# Main_BoardV4.net
KiCad netlist of a schematic drawn in EAGLE
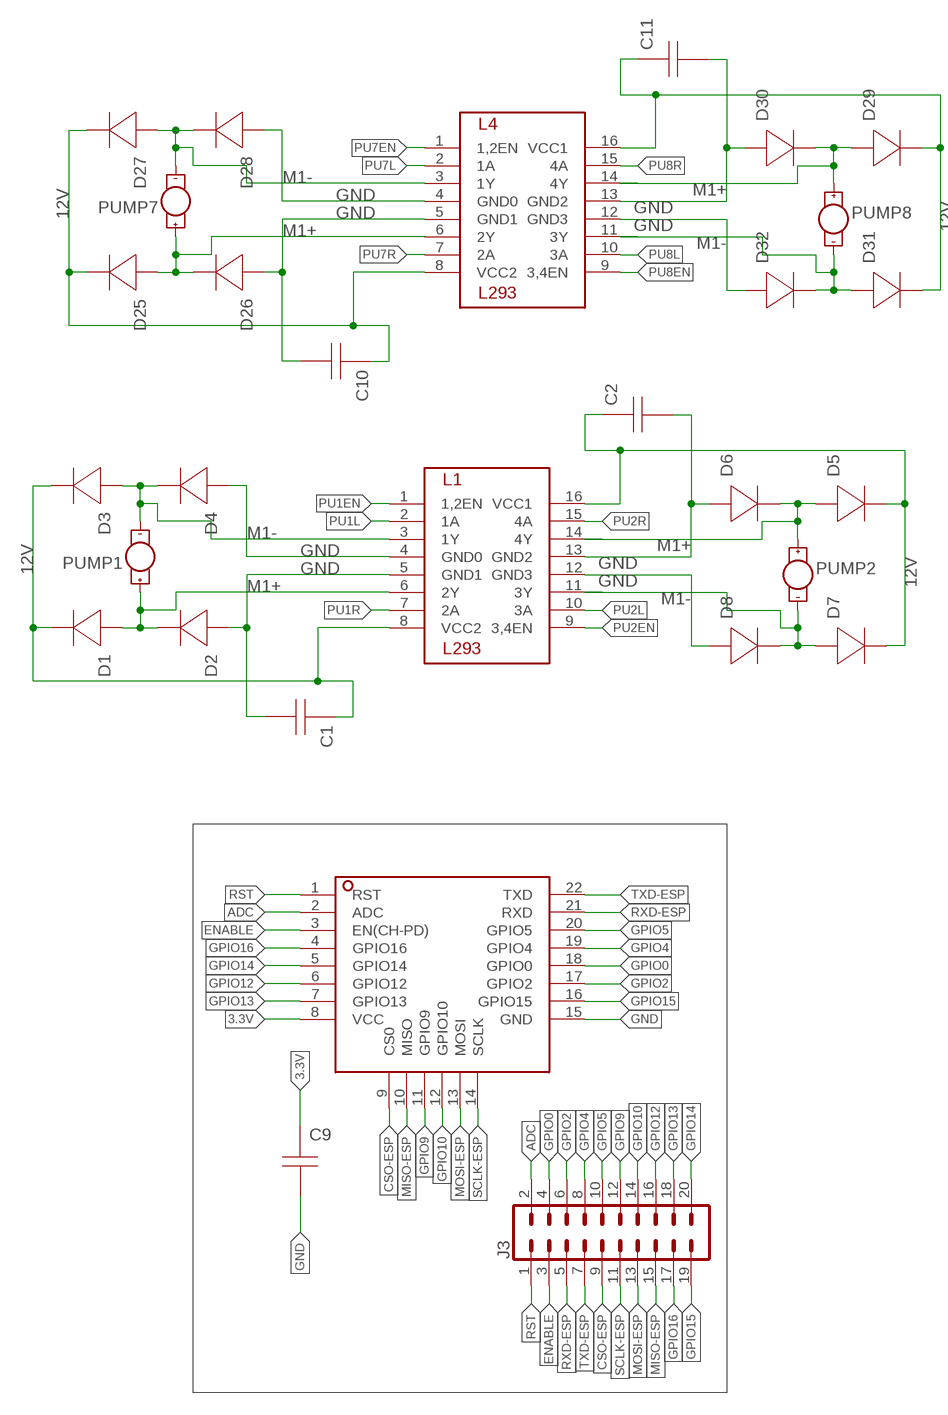
[diagram p0: schematic, sheet 1, part 1 of 2]
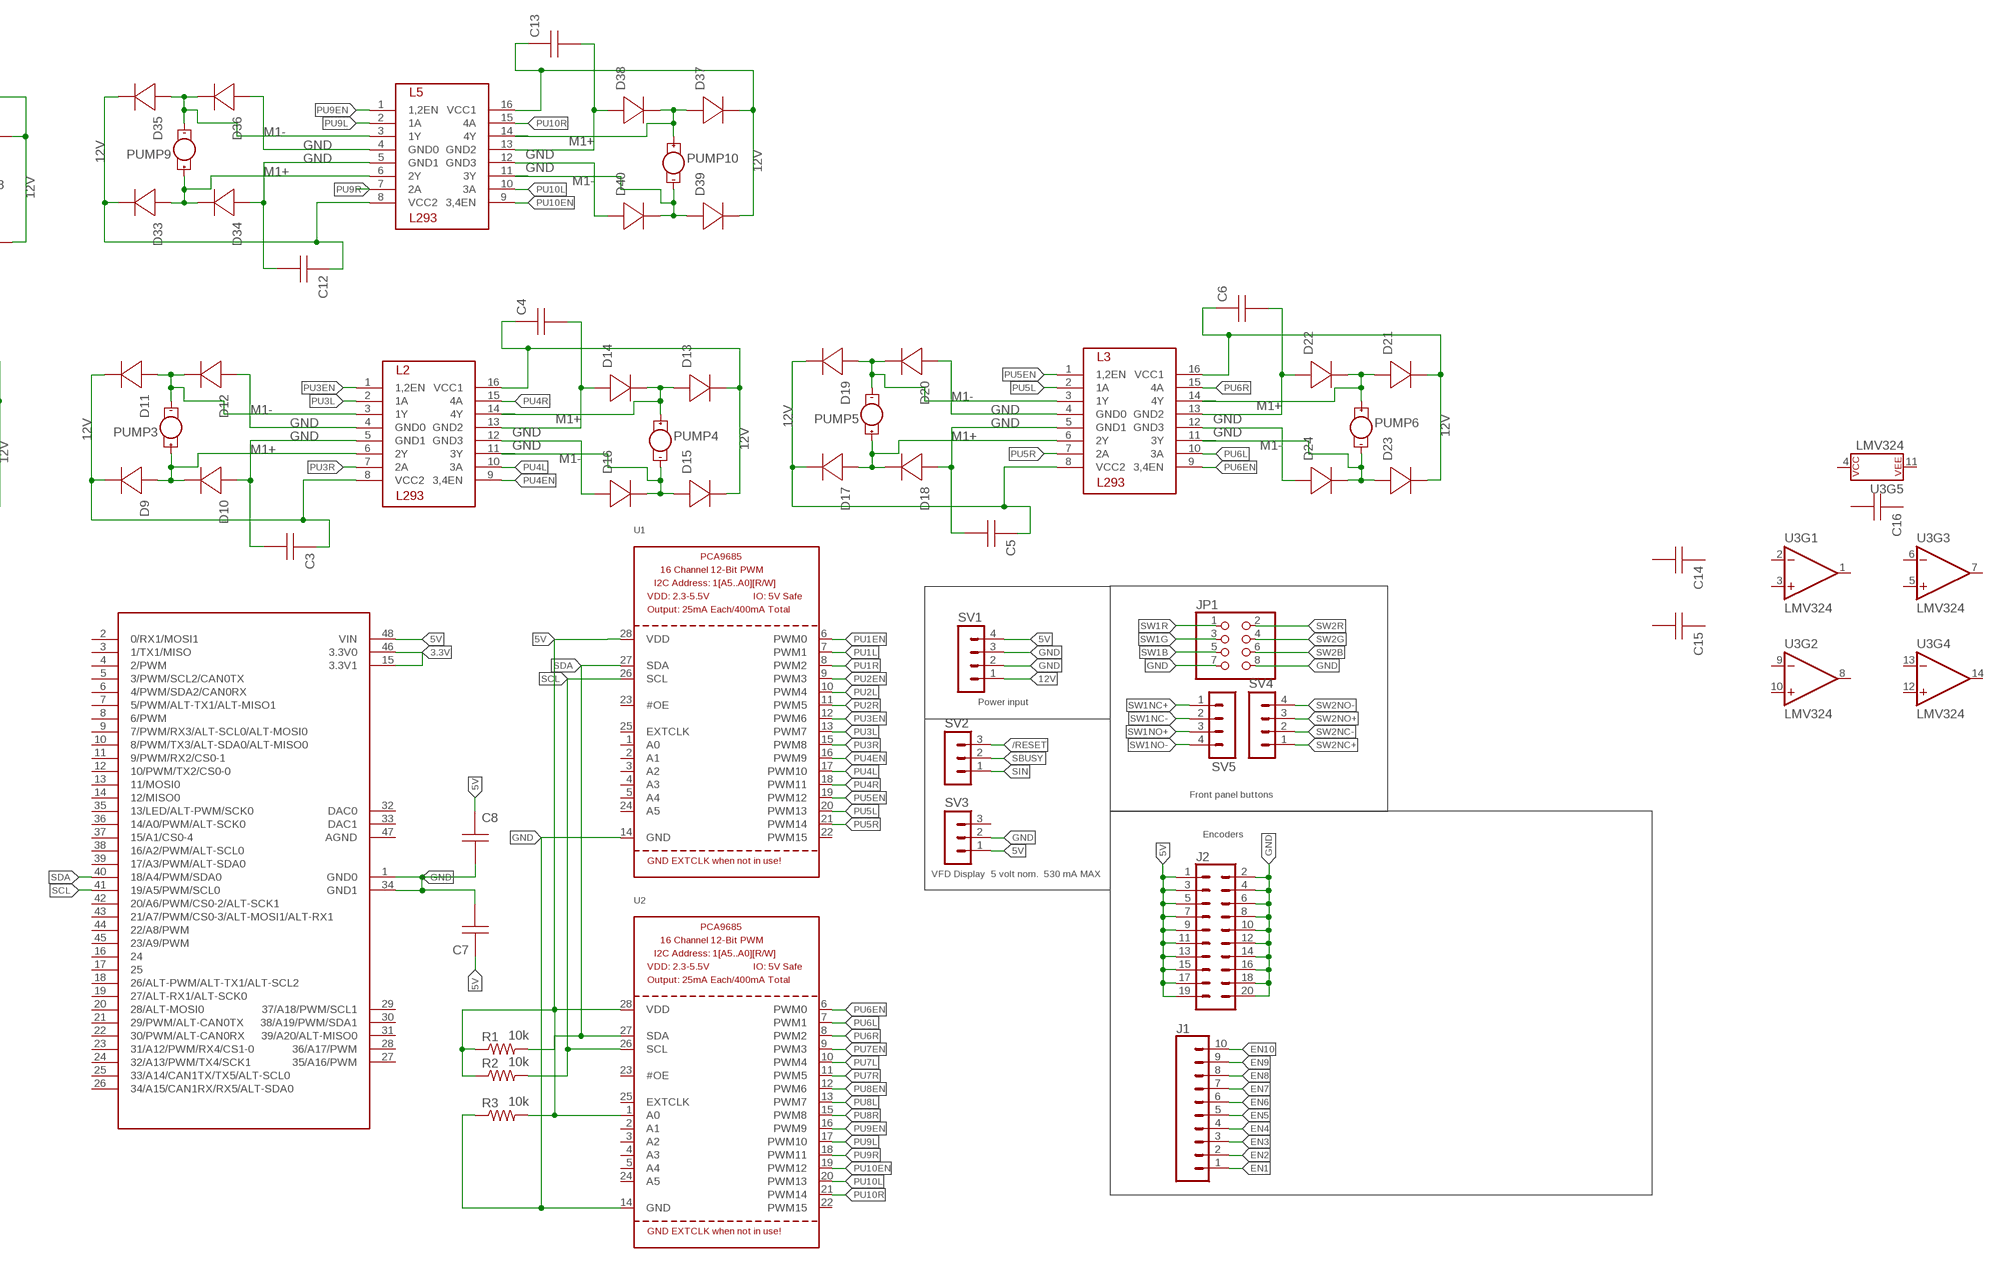
[diagram p1: schematic, sheet 1, part 2 of 2]

(export (version "E")
  (design (tool "Eeschema 10.0.6"))
  (components
    (comp (ref "C1")
      (value "CAP")
      (footprint "eagle-import:C0805")
      (libsource (lib "eagle-import") (part "CAP"))
    )
    (comp (ref "C2")
      (value "CAP")
      (footprint "eagle-import:C0805")
      (libsource (lib "eagle-import") (part "CAP"))
    )
    (comp (ref "C3")
      (value "CAP")
      (footprint "eagle-import:C0805")
      (libsource (lib "eagle-import") (part "CAP"))
    )
    (comp (ref "C4")
      (value "CAP")
      (footprint "eagle-import:C0805")
      (libsource (lib "eagle-import") (part "CAP"))
    )
    (comp (ref "C5")
      (value "CAP")
      (footprint "eagle-import:C0805")
      (libsource (lib "eagle-import") (part "CAP"))
    )
    (comp (ref "C6")
      (value "CAP")
      (footprint "eagle-import:C0805")
      (libsource (lib "eagle-import") (part "CAP"))
    )
    (comp (ref "C7")
      (value "CAP")
      (footprint "eagle-import:C0805")
      (libsource (lib "eagle-import") (part "CAP"))
    )
    (comp (ref "C8")
      (value "CAP")
      (footprint "eagle-import:C0805")
      (libsource (lib "eagle-import") (part "CAP"))
    )
    (comp (ref "C9")
      (value "CAP")
      (footprint "eagle-import:C0805")
      (libsource (lib "eagle-import") (part "CAP"))
    )
    (comp (ref "C10")
      (value "CAP")
      (footprint "eagle-import:C0805")
      (libsource (lib "eagle-import") (part "CAP"))
    )
    (comp (ref "C11")
      (value "CAP")
      (footprint "eagle-import:C0805")
      (libsource (lib "eagle-import") (part "CAP"))
    )
    (comp (ref "C12")
      (value "CAP")
      (footprint "eagle-import:C0805")
      (libsource (lib "eagle-import") (part "CAP"))
    )
    (comp (ref "C13")
      (value "CAP")
      (footprint "eagle-import:C0805")
      (libsource (lib "eagle-import") (part "CAP"))
    )
    (comp (ref "C14")
      (value "CAP")
      (footprint "eagle-import:C0805")
      (libsource (lib "eagle-import") (part "CAP"))
    )
    (comp (ref "C15")
      (value "CAP")
      (footprint "eagle-import:C0805")
      (libsource (lib "eagle-import") (part "CAP"))
    )
    (comp (ref "C16")
      (value "CAP")
      (footprint "eagle-import:C0805")
      (libsource (lib "eagle-import") (part "CAP"))
    )
    (comp (ref "D1")
      (value "UPR5E3-DIODE")
      (footprint "eagle-import:DIOC4519X114")
      (libsource (lib "eagle-import") (part "UPR5E3-DIODE"))
    )
    (comp (ref "D2")
      (value "UPR5E3-DIODE")
      (footprint "eagle-import:DIOC4519X114")
      (libsource (lib "eagle-import") (part "UPR5E3-DIODE"))
    )
    (comp (ref "D3")
      (value "UPR5E3-DIODE")
      (footprint "eagle-import:DIOC4519X114")
      (libsource (lib "eagle-import") (part "UPR5E3-DIODE"))
    )
    (comp (ref "D4")
      (value "UPR5E3-DIODE")
      (footprint "eagle-import:DIOC4519X114")
      (libsource (lib "eagle-import") (part "UPR5E3-DIODE"))
    )
    (comp (ref "D5")
      (value "UPR5E3-DIODE")
      (footprint "eagle-import:DIOC4519X114")
      (libsource (lib "eagle-import") (part "UPR5E3-DIODE"))
    )
    (comp (ref "D6")
      (value "UPR5E3-DIODE")
      (footprint "eagle-import:DIOC4519X114")
      (libsource (lib "eagle-import") (part "UPR5E3-DIODE"))
    )
    (comp (ref "D7")
      (value "UPR5E3-DIODE")
      (footprint "eagle-import:DIOC4519X114")
      (libsource (lib "eagle-import") (part "UPR5E3-DIODE"))
    )
    (comp (ref "D8")
      (value "UPR5E3-DIODE")
      (footprint "eagle-import:DIOC4519X114")
      (libsource (lib "eagle-import") (part "UPR5E3-DIODE"))
    )
    (comp (ref "D9")
      (value "UPR5E3-DIODE")
      (footprint "eagle-import:DIOC4519X114")
      (libsource (lib "eagle-import") (part "UPR5E3-DIODE"))
    )
    (comp (ref "D10")
      (value "UPR5E3-DIODE")
      (footprint "eagle-import:DIOC4519X114")
      (libsource (lib "eagle-import") (part "UPR5E3-DIODE"))
    )
    (comp (ref "D11")
      (value "UPR5E3-DIODE")
      (footprint "eagle-import:DIOC4519X114")
      (libsource (lib "eagle-import") (part "UPR5E3-DIODE"))
    )
    (comp (ref "D12")
      (value "UPR5E3-DIODE")
      (footprint "eagle-import:DIOC4519X114")
      (libsource (lib "eagle-import") (part "UPR5E3-DIODE"))
    )
    (comp (ref "D13")
      (value "UPR5E3-DIODE")
      (footprint "eagle-import:DIOC4519X114")
      (libsource (lib "eagle-import") (part "UPR5E3-DIODE"))
    )
    (comp (ref "D14")
      (value "UPR5E3-DIODE")
      (footprint "eagle-import:DIOC4519X114")
      (libsource (lib "eagle-import") (part "UPR5E3-DIODE"))
    )
    (comp (ref "D15")
      (value "UPR5E3-DIODE")
      (footprint "eagle-import:DIOC4519X114")
      (libsource (lib "eagle-import") (part "UPR5E3-DIODE"))
    )
    (comp (ref "D16")
      (value "UPR5E3-DIODE")
      (footprint "eagle-import:DIOC4519X114")
      (libsource (lib "eagle-import") (part "UPR5E3-DIODE"))
    )
    (comp (ref "D17")
      (value "UPR5E3-DIODE")
      (footprint "eagle-import:DIOC4519X114")
      (libsource (lib "eagle-import") (part "UPR5E3-DIODE"))
    )
    (comp (ref "D18")
      (value "UPR5E3-DIODE")
      (footprint "eagle-import:DIOC4519X114")
      (libsource (lib "eagle-import") (part "UPR5E3-DIODE"))
    )
    (comp (ref "D19")
      (value "UPR5E3-DIODE")
      (footprint "eagle-import:DIOC4519X114")
      (libsource (lib "eagle-import") (part "UPR5E3-DIODE"))
    )
    (comp (ref "D20")
      (value "UPR5E3-DIODE")
      (footprint "eagle-import:DIOC4519X114")
      (libsource (lib "eagle-import") (part "UPR5E3-DIODE"))
    )
    (comp (ref "D21")
      (value "UPR5E3-DIODE")
      (footprint "eagle-import:DIOC4519X114")
      (libsource (lib "eagle-import") (part "UPR5E3-DIODE"))
    )
    (comp (ref "D22")
      (value "UPR5E3-DIODE")
      (footprint "eagle-import:DIOC4519X114")
      (libsource (lib "eagle-import") (part "UPR5E3-DIODE"))
    )
    (comp (ref "D23")
      (value "UPR5E3-DIODE")
      (footprint "eagle-import:DIOC4519X114")
      (libsource (lib "eagle-import") (part "UPR5E3-DIODE"))
    )
    (comp (ref "D24")
      (value "UPR5E3-DIODE")
      (footprint "eagle-import:DIOC4519X114")
      (libsource (lib "eagle-import") (part "UPR5E3-DIODE"))
    )
    (comp (ref "D25")
      (value "UPR5E3-DIODE")
      (footprint "eagle-import:DIOC4519X114")
      (libsource (lib "eagle-import") (part "UPR5E3-DIODE"))
    )
    (comp (ref "D26")
      (value "UPR5E3-DIODE")
      (footprint "eagle-import:DIOC4519X114")
      (libsource (lib "eagle-import") (part "UPR5E3-DIODE"))
    )
    (comp (ref "D27")
      (value "UPR5E3-DIODE")
      (footprint "eagle-import:DIOC4519X114")
      (libsource (lib "eagle-import") (part "UPR5E3-DIODE"))
    )
    (comp (ref "D28")
      (value "UPR5E3-DIODE")
      (footprint "eagle-import:DIOC4519X114")
      (libsource (lib "eagle-import") (part "UPR5E3-DIODE"))
    )
    (comp (ref "D29")
      (value "UPR5E3-DIODE")
      (footprint "eagle-import:DIOC4519X114")
      (libsource (lib "eagle-import") (part "UPR5E3-DIODE"))
    )
    (comp (ref "D30")
      (value "UPR5E3-DIODE")
      (footprint "eagle-import:DIOC4519X114")
      (libsource (lib "eagle-import") (part "UPR5E3-DIODE"))
    )
    (comp (ref "D31")
      (value "UPR5E3-DIODE")
      (footprint "eagle-import:DIOC4519X114")
      (libsource (lib "eagle-import") (part "UPR5E3-DIODE"))
    )
    (comp (ref "D32")
      (value "UPR5E3-DIODE")
      (footprint "eagle-import:DIOC4519X114")
      (libsource (lib "eagle-import") (part "UPR5E3-DIODE"))
    )
    (comp (ref "D33")
      (value "UPR5E3-DIODE")
      (footprint "eagle-import:DIOC4519X114")
      (libsource (lib "eagle-import") (part "UPR5E3-DIODE"))
    )
    (comp (ref "D34")
      (value "UPR5E3-DIODE")
      (footprint "eagle-import:DIOC4519X114")
      (libsource (lib "eagle-import") (part "UPR5E3-DIODE"))
    )
    (comp (ref "D35")
      (value "UPR5E3-DIODE")
      (footprint "eagle-import:DIOC4519X114")
      (libsource (lib "eagle-import") (part "UPR5E3-DIODE"))
    )
    (comp (ref "D36")
      (value "UPR5E3-DIODE")
      (footprint "eagle-import:DIOC4519X114")
      (libsource (lib "eagle-import") (part "UPR5E3-DIODE"))
    )
    (comp (ref "D37")
      (value "UPR5E3-DIODE")
      (footprint "eagle-import:DIOC4519X114")
      (libsource (lib "eagle-import") (part "UPR5E3-DIODE"))
    )
    (comp (ref "D38")
      (value "UPR5E3-DIODE")
      (footprint "eagle-import:DIOC4519X114")
      (libsource (lib "eagle-import") (part "UPR5E3-DIODE"))
    )
    (comp (ref "D39")
      (value "UPR5E3-DIODE")
      (footprint "eagle-import:DIOC4519X114")
      (libsource (lib "eagle-import") (part "UPR5E3-DIODE"))
    )
    (comp (ref "D40")
      (value "UPR5E3-DIODE")
      (footprint "eagle-import:DIOC4519X114")
      (libsource (lib "eagle-import") (part "UPR5E3-DIODE"))
    )
    (comp (ref "ESP1")
      (value "ESP8266")
      (footprint "eagle-import:ESP8266MOD")
      (libsource (lib "eagle-import") (part "ESP8266"))
    )
    (comp (ref "J1")
      (value "CONN_10NO_SILK_PTH_FEMALE")
      (footprint "eagle-import:1X10_NO_SILK")
      (libsource (lib "eagle-import") (part "CONN_10NO_SILK_PTH_FEMALE"))
    )
    (comp (ref "J2")
      (value "CONN_10X2NOSILK")
      (footprint "eagle-import:2X10_NOSILK")
      (libsource (lib "eagle-import") (part "CONN_10X2NOSILK"))
    )
    (comp (ref "J3")
      (value "CONN_10X22X10_LOCK")
      (footprint "eagle-import:2X10_LOCK")
      (libsource (lib "eagle-import") (part "CONN_10X22X10_LOCK"))
    )
    (comp (ref "JP1")
      (value "PINHD-2X4")
      (footprint "eagle-import:2X04")
      (libsource (lib "eagle-import") (part "PINHD-2X4"))
    )
    (comp (ref "L1")
      (value "L293")
      (footprint "eagle-import:DIP762W53P254L1969H508Q16B")
      (libsource (lib "eagle-import") (part "L293"))
    )
    (comp (ref "L2")
      (value "L293")
      (footprint "eagle-import:DIP762W53P254L1969H508Q16B")
      (libsource (lib "eagle-import") (part "L293"))
    )
    (comp (ref "L3")
      (value "L293")
      (footprint "eagle-import:DIP762W53P254L1969H508Q16B")
      (libsource (lib "eagle-import") (part "L293"))
    )
    (comp (ref "L4")
      (value "L293")
      (footprint "eagle-import:DIP762W53P254L1969H508Q16B")
      (libsource (lib "eagle-import") (part "L293"))
    )
    (comp (ref "L5")
      (value "L293")
      (footprint "eagle-import:DIP762W53P254L1969H508Q16B")
      (libsource (lib "eagle-import") (part "L293"))
    )
    (comp (ref "PUMP1")
      (value "PUMPS")
      (footprint "eagle-import:1X2_HEADER")
      (libsource (lib "eagle-import") (part "PUMPS"))
    )
    (comp (ref "PUMP2")
      (value "PUMPS")
      (footprint "eagle-import:1X2_HEADER")
      (libsource (lib "eagle-import") (part "PUMPS"))
    )
    (comp (ref "PUMP3")
      (value "PUMPS")
      (footprint "eagle-import:1X2_HEADER")
      (libsource (lib "eagle-import") (part "PUMPS"))
    )
    (comp (ref "PUMP4")
      (value "PUMPS")
      (footprint "eagle-import:1X2_HEADER")
      (libsource (lib "eagle-import") (part "PUMPS"))
    )
    (comp (ref "PUMP5")
      (value "PUMPS")
      (footprint "eagle-import:1X2_HEADER")
      (libsource (lib "eagle-import") (part "PUMPS"))
    )
    (comp (ref "PUMP6")
      (value "PUMPS")
      (footprint "eagle-import:1X2_HEADER")
      (libsource (lib "eagle-import") (part "PUMPS"))
    )
    (comp (ref "PUMP7")
      (value "PUMPS")
      (footprint "eagle-import:1X2_HEADER")
      (libsource (lib "eagle-import") (part "PUMPS"))
    )
    (comp (ref "PUMP8")
      (value "PUMPS")
      (footprint "eagle-import:1X2_HEADER")
      (libsource (lib "eagle-import") (part "PUMPS"))
    )
    (comp (ref "PUMP9")
      (value "PUMPS")
      (footprint "eagle-import:1X2_HEADER")
      (libsource (lib "eagle-import") (part "PUMPS"))
    )
    (comp (ref "PUMP10")
      (value "PUMPS")
      (footprint "eagle-import:1X2_HEADER")
      (libsource (lib "eagle-import") (part "PUMPS"))
    )
    (comp (ref "R1")
      (value "10k")
      (footprint "eagle-import:R0402")
      (libsource (lib "eagle-import") (part "R-US_R0402"))
    )
    (comp (ref "R2")
      (value "10k")
      (footprint "eagle-import:R0402")
      (libsource (lib "eagle-import") (part "R-US_R0402"))
    )
    (comp (ref "R3")
      (value "10k")
      (footprint "eagle-import:R0402")
      (libsource (lib "eagle-import") (part "R-US_R0402"))
    )
    (comp (ref "SV1")
      (value "MA04-1")
      (footprint "eagle-import:MA04-1")
      (libsource (lib "eagle-import") (part "MA04-1"))
    )
    (comp (ref "SV2")
      (value "MA03-1")
      (footprint "eagle-import:MA03-1")
      (libsource (lib "eagle-import") (part "MA03-1"))
    )
    (comp (ref "SV3")
      (value "MA03-1")
      (footprint "eagle-import:MA03-1")
      (libsource (lib "eagle-import") (part "MA03-1"))
    )
    (comp (ref "SV4")
      (value "MA04-1")
      (footprint "eagle-import:MA04-1")
      (libsource (lib "eagle-import") (part "MA04-1"))
    )
    (comp (ref "SV5")
      (value "MA04-1")
      (footprint "eagle-import:MA04-1")
      (libsource (lib "eagle-import") (part "MA04-1"))
    )
    (comp (ref "TEENSY1")
      (value "TEENSY_3.5")
      (footprint "eagle-import:DIP1524W60P254L6350H635Q48A")
      (libsource (lib "eagle-import") (part "TEENSY_3.5"))
    )
    (comp (ref "U1")
      (value "PCA9685")
      (footprint "eagle-import:TSSOP28")
      (libsource (lib "eagle-import") (part "PCA9685"))
    )
    (comp (ref "U2")
      (value "PCA9685")
      (footprint "eagle-import:TSSOP28")
      (libsource (lib "eagle-import") (part "PCA9685"))
    )
    (comp (ref "U3")
      (value "LMV324")
      (footprint "eagle-import:SO14")
      (libsource (lib "eagle-import") (part "LMV324"))
    )
  )
  (nets
    (net (code "1") (name "/AGND") (class "Default")
      (node (ref "TEENSY1") (pin "47") (pinfunction "AGND_47") (pintype "power_in"))
    )
    (net (code "2") (name "/M1+") (class "Default")
      (node (ref "D1") (pin "2") (pinfunction "+_2") (pintype "passive"))
      (node (ref "D10") (pin "1") (pinfunction "-_1") (pintype "passive"))
      (node (ref "D13") (pin "2") (pinfunction "+_2") (pintype "passive"))
      (node (ref "D14") (pin "1") (pinfunction "-_1") (pintype "passive"))
      (node (ref "D17") (pin "2") (pinfunction "+_2") (pintype "passive"))
      (node (ref "D18") (pin "1") (pinfunction "-_1") (pintype "passive"))
      (node (ref "D2") (pin "1") (pinfunction "-_1") (pintype "passive"))
      (node (ref "D21") (pin "2") (pinfunction "+_2") (pintype "passive"))
      (node (ref "D22") (pin "1") (pinfunction "-_1") (pintype "passive"))
      (node (ref "D25") (pin "2") (pinfunction "+_2") (pintype "passive"))
      (node (ref "D26") (pin "1") (pinfunction "-_1") (pintype "passive"))
      (node (ref "D29") (pin "2") (pinfunction "+_2") (pintype "passive"))
      (node (ref "D30") (pin "1") (pinfunction "-_1") (pintype "passive"))
      (node (ref "D33") (pin "2") (pinfunction "+_2") (pintype "passive"))
      (node (ref "D34") (pin "1") (pinfunction "-_1") (pintype "passive"))
      (node (ref "D37") (pin "2") (pinfunction "+_2") (pintype "passive"))
      (node (ref "D38") (pin "1") (pinfunction "-_1") (pintype "passive"))
      (node (ref "D5") (pin "2") (pinfunction "+_2") (pintype "passive"))
      (node (ref "D6") (pin "1") (pinfunction "-_1") (pintype "passive"))
      (node (ref "D9") (pin "2") (pinfunction "+_2") (pintype "passive"))
      (node (ref "L1") (pin "14") (pinfunction "4Y_14") (pintype "bidirectional"))
      (node (ref "L1") (pin "6") (pinfunction "2Y_6") (pintype "bidirectional"))
      (node (ref "L2") (pin "14") (pinfunction "4Y_14") (pintype "bidirectional"))
      (node (ref "L2") (pin "6") (pinfunction "2Y_6") (pintype "bidirectional"))
      (node (ref "L3") (pin "14") (pinfunction "4Y_14") (pintype "bidirectional"))
      (node (ref "L3") (pin "6") (pinfunction "2Y_6") (pintype "bidirectional"))
      (node (ref "L4") (pin "14") (pinfunction "4Y_14") (pintype "bidirectional"))
      (node (ref "L4") (pin "6") (pinfunction "2Y_6") (pintype "bidirectional"))
      (node (ref "L5") (pin "14") (pinfunction "4Y_14") (pintype "bidirectional"))
      (node (ref "L5") (pin "6") (pinfunction "2Y_6") (pintype "bidirectional"))
      (node (ref "PUMP1") (pin "1") (pinfunction "+_1") (pintype "bidirectional"))
      (node (ref "PUMP10") (pin "1") (pinfunction "+_1") (pintype "bidirectional"))
      (node (ref "PUMP2") (pin "1") (pinfunction "+_1") (pintype "bidirectional"))
      (node (ref "PUMP3") (pin "1") (pinfunction "+_1") (pintype "bidirectional"))
      (node (ref "PUMP4") (pin "1") (pinfunction "+_1") (pintype "bidirectional"))
      (node (ref "PUMP5") (pin "1") (pinfunction "+_1") (pintype "bidirectional"))
      (node (ref "PUMP6") (pin "1") (pinfunction "+_1") (pintype "bidirectional"))
      (node (ref "PUMP7") (pin "1") (pinfunction "+_1") (pintype "bidirectional"))
      (node (ref "PUMP8") (pin "1") (pinfunction "+_1") (pintype "bidirectional"))
      (node (ref "PUMP9") (pin "1") (pinfunction "+_1") (pintype "bidirectional"))
    )
    (net (code "3") (name "/M1-") (class "Default")
      (node (ref "D11") (pin "2") (pinfunction "+_2") (pintype "passive"))
      (node (ref "D12") (pin "1") (pinfunction "-_1") (pintype "passive"))
      (node (ref "D15") (pin "2") (pinfunction "+_2") (pintype "passive"))
      (node (ref "D16") (pin "1") (pinfunction "-_1") (pintype "passive"))
      (node (ref "D19") (pin "2") (pinfunction "+_2") (pintype "passive"))
      (node (ref "D20") (pin "1") (pinfunction "-_1") (pintype "passive"))
      (node (ref "D23") (pin "2") (pinfunction "+_2") (pintype "passive"))
      (node (ref "D24") (pin "1") (pinfunction "-_1") (pintype "passive"))
      (node (ref "D27") (pin "2") (pinfunction "+_2") (pintype "passive"))
      (node (ref "D28") (pin "1") (pinfunction "-_1") (pintype "passive"))
      (node (ref "D3") (pin "2") (pinfunction "+_2") (pintype "passive"))
      (node (ref "D31") (pin "2") (pinfunction "+_2") (pintype "passive"))
      (node (ref "D32") (pin "1") (pinfunction "-_1") (pintype "passive"))
      (node (ref "D35") (pin "2") (pinfunction "+_2") (pintype "passive"))
      (node (ref "D36") (pin "1") (pinfunction "-_1") (pintype "passive"))
      (node (ref "D39") (pin "2") (pinfunction "+_2") (pintype "passive"))
      (node (ref "D4") (pin "1") (pinfunction "-_1") (pintype "passive"))
      (node (ref "D40") (pin "1") (pinfunction "-_1") (pintype "passive"))
      (node (ref "D7") (pin "2") (pinfunction "+_2") (pintype "passive"))
      (node (ref "D8") (pin "1") (pinfunction "-_1") (pintype "passive"))
      (node (ref "L1") (pin "11") (pinfunction "3Y_11") (pintype "bidirectional"))
      (node (ref "L1") (pin "3") (pinfunction "1Y_3") (pintype "bidirectional"))
      (node (ref "L2") (pin "11") (pinfunction "3Y_11") (pintype "bidirectional"))
      (node (ref "L2") (pin "3") (pinfunction "1Y_3") (pintype "bidirectional"))
      (node (ref "L3") (pin "11") (pinfunction "3Y_11") (pintype "bidirectional"))
      (node (ref "L3") (pin "3") (pinfunction "1Y_3") (pintype "bidirectional"))
      (node (ref "L4") (pin "11") (pinfunction "3Y_11") (pintype "bidirectional"))
      (node (ref "L4") (pin "3") (pinfunction "1Y_3") (pintype "bidirectional"))
      (node (ref "L5") (pin "11") (pinfunction "3Y_11") (pintype "bidirectional"))
      (node (ref "L5") (pin "3") (pinfunction "1Y_3") (pintype "bidirectional"))
      (node (ref "PUMP1") (pin "2") (pinfunction "-_2") (pintype "bidirectional"))
      (node (ref "PUMP10") (pin "2") (pinfunction "-_2") (pintype "bidirectional"))
      (node (ref "PUMP2") (pin "2") (pinfunction "-_2") (pintype "bidirectional"))
      (node (ref "PUMP3") (pin "2") (pinfunction "-_2") (pintype "bidirectional"))
      (node (ref "PUMP4") (pin "2") (pinfunction "-_2") (pintype "bidirectional"))
      (node (ref "PUMP5") (pin "2") (pinfunction "-_2") (pintype "bidirectional"))
      (node (ref "PUMP6") (pin "2") (pinfunction "-_2") (pintype "bidirectional"))
      (node (ref "PUMP7") (pin "2") (pinfunction "-_2") (pintype "bidirectional"))
      (node (ref "PUMP8") (pin "2") (pinfunction "-_2") (pintype "bidirectional"))
      (node (ref "PUMP9") (pin "2") (pinfunction "-_2") (pintype "bidirectional"))
    )
    (net (code "4") (name "3.3V") (class "Default")
      (node (ref "C9") (pin "1") (pinfunction "A_1") (pintype "passive"))
      (node (ref "ESP1") (pin "8") (pinfunction "VCC_8") (pintype "bidirectional"))
      (node (ref "TEENSY1") (pin "15") (pinfunction "3.3V1_15") (pintype "power_in"))
      (node (ref "TEENSY1") (pin "46") (pinfunction "3.3V0_46") (pintype "power_in"))
    )
    (net (code "5") (name "5V") (class "Default")
      (node (ref "C7") (pin "1") (pinfunction "A_1") (pintype "passive"))
      (node (ref "C8") (pin "1") (pinfunction "A_1") (pintype "passive"))
      (node (ref "J2") (pin "1") (pinfunction "1_1") (pintype "passive"))
      (node (ref "J2") (pin "11") (pinfunction "11_11") (pintype "passive"))
      (node (ref "J2") (pin "13") (pinfunction "13_13") (pintype "passive"))
      (node (ref "J2") (pin "15") (pinfunction "15_15") (pintype "passive"))
      (node (ref "J2") (pin "17") (pinfunction "17_17") (pintype "passive"))
      (node (ref "J2") (pin "19") (pinfunction "19_19") (pintype "passive"))
      (node (ref "J2") (pin "3") (pinfunction "3_3") (pintype "passive"))
      (node (ref "J2") (pin "5") (pinfunction "5_5") (pintype "passive"))
      (node (ref "J2") (pin "7") (pinfunction "7_7") (pintype "passive"))
      (node (ref "J2") (pin "9") (pinfunction "9_9") (pintype "passive"))
      (node (ref "R1") (pin "1") (pinfunction "1_1") (pintype "passive"))
      (node (ref "R2") (pin "1") (pinfunction "1_1") (pintype "passive"))
      (node (ref "R3") (pin "2") (pinfunction "2_2") (pintype "passive"))
      (node (ref "SV1") (pin "4") (pinfunction "4_4") (pintype "passive"))
      (node (ref "SV3") (pin "1") (pinfunction "1_1") (pintype "passive"))
      (node (ref "TEENSY1") (pin "48") (pinfunction "VIN_48") (pintype "power_in"))
      (node (ref "U1") (pin "28") (pinfunction "VDD_28") (pintype "power_in"))
      (node (ref "U2") (pin "1") (pinfunction "A0_1") (pintype "bidirectional"))
      (node (ref "U2") (pin "28") (pinfunction "VDD_28") (pintype "power_in"))
    )
    (net (code "6") (name "12V") (class "Default")
      (node (ref "C1") (pin "1") (pinfunction "A_1") (pintype "passive"))
      (node (ref "C10") (pin "1") (pinfunction "A_1") (pintype "passive"))
      (node (ref "C11") (pin "1") (pinfunction "A_1") (pintype "passive"))
      (node (ref "C12") (pin "1") (pinfunction "A_1") (pintype "passive"))
      (node (ref "C13") (pin "1") (pinfunction "A_1") (pintype "passive"))
      (node (ref "C2") (pin "1") (pinfunction "A_1") (pintype "passive"))
      (node (ref "C3") (pin "1") (pinfunction "A_1") (pintype "passive"))
      (node (ref "C4") (pin "1") (pinfunction "A_1") (pintype "passive"))
      (node (ref "C5") (pin "1") (pinfunction "A_1") (pintype "passive"))
      (node (ref "C6") (pin "1") (pinfunction "A_1") (pintype "passive"))
      (node (ref "D1") (pin "1") (pinfunction "-_1") (pintype "passive"))
      (node (ref "D11") (pin "1") (pinfunction "-_1") (pintype "passive"))
      (node (ref "D13") (pin "1") (pinfunction "-_1") (pintype "passive"))
      (node (ref "D15") (pin "1") (pinfunction "-_1") (pintype "passive"))
      (node (ref "D17") (pin "1") (pinfunction "-_1") (pintype "passive"))
      (node (ref "D19") (pin "1") (pinfunction "-_1") (pintype "passive"))
      (node (ref "D21") (pin "1") (pinfunction "-_1") (pintype "passive"))
      (node (ref "D23") (pin "1") (pinfunction "-_1") (pintype "passive"))
      (node (ref "D25") (pin "1") (pinfunction "-_1") (pintype "passive"))
      (node (ref "D27") (pin "1") (pinfunction "-_1") (pintype "passive"))
      (node (ref "D29") (pin "1") (pinfunction "-_1") (pintype "passive"))
      (node (ref "D3") (pin "1") (pinfunction "-_1") (pintype "passive"))
      (node (ref "D31") (pin "1") (pinfunction "-_1") (pintype "passive"))
      (node (ref "D33") (pin "1") (pinfunction "-_1") (pintype "passive"))
      (node (ref "D35") (pin "1") (pinfunction "-_1") (pintype "passive"))
      (node (ref "D37") (pin "1") (pinfunction "-_1") (pintype "passive"))
      (node (ref "D39") (pin "1") (pinfunction "-_1") (pintype "passive"))
      (node (ref "D5") (pin "1") (pinfunction "-_1") (pintype "passive"))
      (node (ref "D7") (pin "1") (pinfunction "-_1") (pintype "passive"))
      (node (ref "D9") (pin "1") (pinfunction "-_1") (pintype "passive"))
      (node (ref "L1") (pin "16") (pinfunction "VCC1_16") (pintype "bidirectional"))
      (node (ref "L1") (pin "8") (pinfunction "VCC2_8") (pintype "bidirectional"))
      (node (ref "L2") (pin "16") (pinfunction "VCC1_16") (pintype "bidirectional"))
      (node (ref "L2") (pin "8") (pinfunction "VCC2_8") (pintype "bidirectional"))
      (node (ref "L3") (pin "16") (pinfunction "VCC1_16") (pintype "bidirectional"))
      (node (ref "L3") (pin "8") (pinfunction "VCC2_8") (pintype "bidirectional"))
      (node (ref "L4") (pin "16") (pinfunction "VCC1_16") (pintype "bidirectional"))
      (node (ref "L4") (pin "8") (pinfunction "VCC2_8") (pintype "bidirectional"))
      (node (ref "L5") (pin "16") (pinfunction "VCC1_16") (pintype "bidirectional"))
      (node (ref "L5") (pin "8") (pinfunction "VCC2_8") (pintype "bidirectional"))
      (node (ref "SV1") (pin "1") (pinfunction "1_1") (pintype "passive"))
    )
    (net (code "7") (name "ADC") (class "Default")
      (node (ref "ESP1") (pin "2") (pinfunction "ADC_2") (pintype "bidirectional"))
      (node (ref "J3") (pin "2") (pinfunction "2_2") (pintype "passive"))
    )
    (net (code "8") (name "CSO-ESP") (class "Default")
      (node (ref "ESP1") (pin "9") (pinfunction "CS0_9") (pintype "bidirectional"))
      (node (ref "J3") (pin "9") (pinfunction "9_9") (pintype "passive"))
    )
    (net (code "9") (name "EN1") (class "Default")
      (node (ref "J1") (pin "1") (pinfunction "1_1") (pintype "passive"))
    )
    (net (code "10") (name "EN2") (class "Default")
      (node (ref "J1") (pin "2") (pinfunction "2_2") (pintype "passive"))
    )
    (net (code "11") (name "EN3") (class "Default")
      (node (ref "J1") (pin "3") (pinfunction "3_3") (pintype "passive"))
    )
    (net (code "12") (name "EN4") (class "Default")
      (node (ref "J1") (pin "4") (pinfunction "4_4") (pintype "passive"))
    )
    (net (code "13") (name "EN5") (class "Default")
      (node (ref "J1") (pin "5") (pinfunction "5_5") (pintype "passive"))
    )
    (net (code "14") (name "EN6") (class "Default")
      (node (ref "J1") (pin "6") (pinfunction "6_6") (pintype "passive"))
    )
    (net (code "15") (name "EN7") (class "Default")
      (node (ref "J1") (pin "7") (pinfunction "7_7") (pintype "passive"))
    )
    (net (code "16") (name "EN8") (class "Default")
      (node (ref "J1") (pin "8") (pinfunction "8_8") (pintype "passive"))
    )
    (net (code "17") (name "EN9") (class "Default")
      (node (ref "J1") (pin "9") (pinfunction "9_9") (pintype "passive"))
    )
    (net (code "18") (name "EN10") (class "Default")
      (node (ref "J1") (pin "10") (pinfunction "10_10") (pintype "passive"))
    )
    (net (code "19") (name "ENABLE") (class "Default")
      (node (ref "ESP1") (pin "3") (pinfunction "EN(CH-PD)_3") (pintype "bidirectional"))
      (node (ref "J3") (pin "3") (pinfunction "3_3") (pintype "passive"))
    )
    (net (code "20") (name "GND") (class "Default")
      (node (ref "C1") (pin "2") (pinfunction "B_2") (pintype "passive"))
      (node (ref "C10") (pin "2") (pinfunction "B_2") (pintype "passive"))
      (node (ref "C11") (pin "2") (pinfunction "B_2") (pintype "passive"))
      (node (ref "C12") (pin "2") (pinfunction "B_2") (pintype "passive"))
      (node (ref "C13") (pin "2") (pinfunction "B_2") (pintype "passive"))
      (node (ref "C2") (pin "2") (pinfunction "B_2") (pintype "passive"))
      (node (ref "C3") (pin "2") (pinfunction "B_2") (pintype "passive"))
      (node (ref "C4") (pin "2") (pinfunction "B_2") (pintype "passive"))
      (node (ref "C5") (pin "2") (pinfunction "B_2") (pintype "passive"))
      (node (ref "C6") (pin "2") (pinfunction "B_2") (pintype "passive"))
      (node (ref "C7") (pin "2") (pinfunction "B_2") (pintype "passive"))
      (node (ref "C8") (pin "2") (pinfunction "B_2") (pintype "passive"))
      (node (ref "C9") (pin "2") (pinfunction "B_2") (pintype "passive"))
      (node (ref "D10") (pin "2") (pinfunction "+_2") (pintype "passive"))
      (node (ref "D12") (pin "2") (pinfunction "+_2") (pintype "passive"))
      (node (ref "D14") (pin "2") (pinfunction "+_2") (pintype "passive"))
      (node (ref "D16") (pin "2") (pinfunction "+_2") (pintype "passive"))
      (node (ref "D18") (pin "2") (pinfunction "+_2") (pintype "passive"))
      (node (ref "D2") (pin "2") (pinfunction "+_2") (pintype "passive"))
      (node (ref "D20") (pin "2") (pinfunction "+_2") (pintype "passive"))
      (node (ref "D22") (pin "2") (pinfunction "+_2") (pintype "passive"))
      (node (ref "D24") (pin "2") (pinfunction "+_2") (pintype "passive"))
      (node (ref "D26") (pin "2") (pinfunction "+_2") (pintype "passive"))
      (node (ref "D28") (pin "2") (pinfunction "+_2") (pintype "passive"))
      (node (ref "D30") (pin "2") (pinfunction "+_2") (pintype "passive"))
      (node (ref "D32") (pin "2") (pinfunction "+_2") (pintype "passive"))
      (node (ref "D34") (pin "2") (pinfunction "+_2") (pintype "passive"))
      (node (ref "D36") (pin "2") (pinfunction "+_2") (pintype "passive"))
      (node (ref "D38") (pin "2") (pinfunction "+_2") (pintype "passive"))
      (node (ref "D4") (pin "2") (pinfunction "+_2") (pintype "passive"))
      (node (ref "D40") (pin "2") (pinfunction "+_2") (pintype "passive"))
      (node (ref "D6") (pin "2") (pinfunction "+_2") (pintype "passive"))
      (node (ref "D8") (pin "2") (pinfunction "+_2") (pintype "passive"))
      (node (ref "ESP1") (pin "15") (pinfunction "GND_15") (pintype "bidirectional"))
      (node (ref "J2") (pin "10") (pinfunction "10_10") (pintype "passive"))
      (node (ref "J2") (pin "12") (pinfunction "12_12") (pintype "passive"))
      (node (ref "J2") (pin "14") (pinfunction "14_14") (pintype "passive"))
      (node (ref "J2") (pin "16") (pinfunction "16_16") (pintype "passive"))
      (node (ref "J2") (pin "18") (pinfunction "18_18") (pintype "passive"))
      (node (ref "J2") (pin "2") (pinfunction "2_2") (pintype "passive"))
      (node (ref "J2") (pin "20") (pinfunction "20_20") (pintype "passive"))
      (node (ref "J2") (pin "4") (pinfunction "4_4") (pintype "passive"))
      (node (ref "J2") (pin "6") (pinfunction "6_6") (pintype "passive"))
      (node (ref "J2") (pin "8") (pinfunction "8_8") (pintype "passive"))
      (node (ref "JP1") (pin "7") (pinfunction "7_7") (pintype "passive"))
      (node (ref "JP1") (pin "8") (pinfunction "8_8") (pintype "passive"))
      (node (ref "L1") (pin "12") (pinfunction "GND3_12") (pintype "bidirectional"))
      (node (ref "L1") (pin "13") (pinfunction "GND2_13") (pintype "bidirectional"))
      (node (ref "L1") (pin "4") (pinfunction "GND0_4") (pintype "bidirectional"))
      (node (ref "L1") (pin "5") (pinfunction "GND1_5") (pintype "bidirectional"))
      (node (ref "L2") (pin "12") (pinfunction "GND3_12") (pintype "bidirectional"))
      (node (ref "L2") (pin "13") (pinfunction "GND2_13") (pintype "bidirectional"))
      (node (ref "L2") (pin "4") (pinfunction "GND0_4") (pintype "bidirectional"))
      (node (ref "L2") (pin "5") (pinfunction "GND1_5") (pintype "bidirectional"))
      (node (ref "L3") (pin "12") (pinfunction "GND3_12") (pintype "bidirectional"))
      (node (ref "L3") (pin "13") (pinfunction "GND2_13") (pintype "bidirectional"))
      (node (ref "L3") (pin "4") (pinfunction "GND0_4") (pintype "bidirectional"))
      (node (ref "L3") (pin "5") (pinfunction "GND1_5") (pintype "bidirectional"))
      (node (ref "L4") (pin "12") (pinfunction "GND3_12") (pintype "bidirectional"))
      (node (ref "L4") (pin "13") (pinfunction "GND2_13") (pintype "bidirectional"))
      (node (ref "L4") (pin "4") (pinfunction "GND0_4") (pintype "bidirectional"))
      (node (ref "L4") (pin "5") (pinfunction "GND1_5") (pintype "bidirectional"))
      (node (ref "L5") (pin "12") (pinfunction "GND3_12") (pintype "bidirectional"))
      (node (ref "L5") (pin "13") (pinfunction "GND2_13") (pintype "bidirectional"))
      (node (ref "L5") (pin "4") (pinfunction "GND0_4") (pintype "bidirectional"))
      (node (ref "L5") (pin "5") (pinfunction "GND1_5") (pintype "bidirectional"))
      (node (ref "R3") (pin "1") (pinfunction "1_1") (pintype "passive"))
      (node (ref "SV1") (pin "2") (pinfunction "2_2") (pintype "passive"))
      (node (ref "SV1") (pin "3") (pinfunction "3_3") (pintype "passive"))
      (node (ref "SV3") (pin "2") (pinfunction "2_2") (pintype "passive"))
      (node (ref "TEENSY1") (pin "1") (pinfunction "GND0_1") (pintype "power_in"))
      (node (ref "TEENSY1") (pin "34") (pinfunction "GND1_34") (pintype "power_in"))
      (node (ref "U1") (pin "14") (pinfunction "GND_14") (pintype "power_in"))
      (node (ref "U2") (pin "14") (pinfunction "GND_14") (pintype "power_in"))
    )
    (net (code "21") (name "GPIO0") (class "Default")
      (node (ref "ESP1") (pin "18") (pinfunction "GPIO0_18") (pintype "bidirectional"))
      (node (ref "J3") (pin "4") (pinfunction "4_4") (pintype "passive"))
    )
    (net (code "22") (name "GPIO2") (class "Default")
      (node (ref "ESP1") (pin "17") (pinfunction "GPIO2_17") (pintype "bidirectional"))
      (node (ref "J3") (pin "6") (pinfunction "6_6") (pintype "passive"))
    )
    (net (code "23") (name "GPIO4") (class "Default")
      (node (ref "ESP1") (pin "19") (pinfunction "GPIO4_19") (pintype "bidirectional"))
      (node (ref "J3") (pin "8") (pinfunction "8_8") (pintype "passive"))
    )
    (net (code "24") (name "GPIO5") (class "Default")
      (node (ref "ESP1") (pin "20") (pinfunction "GPIO5_20") (pintype "bidirectional"))
      (node (ref "J3") (pin "10") (pinfunction "10_10") (pintype "passive"))
    )
    (net (code "25") (name "GPIO9") (class "Default")
      (node (ref "ESP1") (pin "11") (pinfunction "GPIO9_11") (pintype "bidirectional"))
      (node (ref "J3") (pin "12") (pinfunction "12_12") (pintype "passive"))
    )
    (net (code "26") (name "GPIO10") (class "Default")
      (node (ref "ESP1") (pin "12") (pinfunction "GPIO10_12") (pintype "bidirectional"))
      (node (ref "J3") (pin "14") (pinfunction "14_14") (pintype "passive"))
    )
    (net (code "27") (name "GPIO12") (class "Default")
      (node (ref "ESP1") (pin "6") (pinfunction "GPIO12_6") (pintype "bidirectional"))
      (node (ref "J3") (pin "16") (pinfunction "16_16") (pintype "passive"))
    )
    (net (code "28") (name "GPIO13") (class "Default")
      (node (ref "ESP1") (pin "7") (pinfunction "GPIO13_7") (pintype "bidirectional"))
      (node (ref "J3") (pin "18") (pinfunction "18_18") (pintype "passive"))
    )
    (net (code "29") (name "GPIO14") (class "Default")
      (node (ref "ESP1") (pin "5") (pinfunction "GPIO14_5") (pintype "bidirectional"))
      (node (ref "J3") (pin "20") (pinfunction "20_20") (pintype "passive"))
    )
    (net (code "30") (name "GPIO15") (class "Default")
      (node (ref "ESP1") (pin "16") (pinfunction "GPIO15_16") (pintype "bidirectional"))
      (node (ref "J3") (pin "19") (pinfunction "19_19") (pintype "passive"))
    )
    (net (code "31") (name "GPIO16") (class "Default")
      (node (ref "ESP1") (pin "4") (pinfunction "GPIO16_4") (pintype "bidirectional"))
      (node (ref "J3") (pin "17") (pinfunction "17_17") (pintype "passive"))
    )
    (net (code "32") (name "MISO-ESP") (class "Default")
      (node (ref "ESP1") (pin "10") (pinfunction "MISO_10") (pintype "bidirectional"))
      (node (ref "J3") (pin "15") (pinfunction "15_15") (pintype "passive"))
    )
    (net (code "33") (name "MOSI-ESP") (class "Default")
      (node (ref "ESP1") (pin "13") (pinfunction "MOSI_13") (pintype "bidirectional"))
      (node (ref "J3") (pin "13") (pinfunction "13_13") (pintype "passive"))
    )
    (net (code "34") (name "PU1EN") (class "Default")
      (node (ref "L1") (pin "1") (pinfunction "1,2EN_1") (pintype "bidirectional"))
      (node (ref "U1") (pin "6") (pinfunction "PWM0_6") (pintype "output"))
    )
    (net (code "35") (name "PU1L") (class "Default")
      (node (ref "L1") (pin "2") (pinfunction "1A_2") (pintype "bidirectional"))
      (node (ref "U1") (pin "7") (pinfunction "PWM1_7") (pintype "output"))
    )
    (net (code "36") (name "PU1R") (class "Default")
      (node (ref "L1") (pin "7") (pinfunction "2A_7") (pintype "bidirectional"))
      (node (ref "U1") (pin "8") (pinfunction "PWM2_8") (pintype "output"))
    )
    (net (code "37") (name "PU2EN") (class "Default")
      (node (ref "L1") (pin "9") (pinfunction "3,4EN_9") (pintype "bidirectional"))
      (node (ref "U1") (pin "9") (pinfunction "PWM3_9") (pintype "output"))
    )
    (net (code "38") (name "PU2L") (class "Default")
      (node (ref "L1") (pin "10") (pinfunction "3A_10") (pintype "bidirectional"))
      (node (ref "U1") (pin "10") (pinfunction "PWM4_10") (pintype "output"))
    )
    (net (code "39") (name "PU2R") (class "Default")
      (node (ref "L1") (pin "15") (pinfunction "4A_15") (pintype "bidirectional"))
      (node (ref "U1") (pin "11") (pinfunction "PWM5_11") (pintype "output"))
    )
    (net (code "40") (name "PU3EN") (class "Default")
      (node (ref "L2") (pin "1") (pinfunction "1,2EN_1") (pintype "bidirectional"))
      (node (ref "U1") (pin "12") (pinfunction "PWM6_12") (pintype "output"))
    )
    (net (code "41") (name "PU3L") (class "Default")
      (node (ref "L2") (pin "2") (pinfunction "1A_2") (pintype "bidirectional"))
      (node (ref "U1") (pin "13") (pinfunction "PWM7_13") (pintype "output"))
    )
    (net (code "42") (name "PU3R") (class "Default")
      (node (ref "L2") (pin "7") (pinfunction "2A_7") (pintype "bidirectional"))
      (node (ref "U1") (pin "15") (pinfunction "PWM8_15") (pintype "output"))
    )
    (net (code "43") (name "PU4EN") (class "Default")
      (node (ref "L2") (pin "9") (pinfunction "3,4EN_9") (pintype "bidirectional"))
      (node (ref "U1") (pin "16") (pinfunction "PWM9_16") (pintype "output"))
    )
    (net (code "44") (name "PU4L") (class "Default")
      (node (ref "L2") (pin "10") (pinfunction "3A_10") (pintype "bidirectional"))
      (node (ref "U1") (pin "17") (pinfunction "PWM10_17") (pintype "output"))
    )
    (net (code "45") (name "PU4R") (class "Default")
      (node (ref "L2") (pin "15") (pinfunction "4A_15") (pintype "bidirectional"))
      (node (ref "U1") (pin "18") (pinfunction "PWM11_18") (pintype "output"))
    )
    (net (code "46") (name "PU5EN") (class "Default")
      (node (ref "L3") (pin "1") (pinfunction "1,2EN_1") (pintype "bidirectional"))
      (node (ref "U1") (pin "19") (pinfunction "PWM12_19") (pintype "output"))
    )
    (net (code "47") (name "PU5L") (class "Default")
      (node (ref "L3") (pin "2") (pinfunction "1A_2") (pintype "bidirectional"))
      (node (ref "U1") (pin "20") (pinfunction "PWM13_20") (pintype "output"))
    )
    (net (code "48") (name "PU5R") (class "Default")
      (node (ref "L3") (pin "7") (pinfunction "2A_7") (pintype "bidirectional"))
      (node (ref "U1") (pin "21") (pinfunction "PWM14_21") (pintype "output"))
    )
    (net (code "49") (name "PU6EN") (class "Default")
      (node (ref "L3") (pin "9") (pinfunction "3,4EN_9") (pintype "bidirectional"))
      (node (ref "U2") (pin "6") (pinfunction "PWM0_6") (pintype "output"))
    )
    (net (code "50") (name "PU6L") (class "Default")
      (node (ref "L3") (pin "10") (pinfunction "3A_10") (pintype "bidirectional"))
      (node (ref "U2") (pin "7") (pinfunction "PWM1_7") (pintype "output"))
    )
    (net (code "51") (name "PU6R") (class "Default")
      (node (ref "L3") (pin "15") (pinfunction "4A_15") (pintype "bidirectional"))
      (node (ref "U2") (pin "8") (pinfunction "PWM2_8") (pintype "output"))
    )
    (net (code "52") (name "PU7EN") (class "Default")
      (node (ref "L4") (pin "1") (pinfunction "1,2EN_1") (pintype "bidirectional"))
      (node (ref "U2") (pin "9") (pinfunction "PWM3_9") (pintype "output"))
    )
    (net (code "53") (name "PU7L") (class "Default")
      (node (ref "L4") (pin "2") (pinfunction "1A_2") (pintype "bidirectional"))
      (node (ref "U2") (pin "10") (pinfunction "PWM4_10") (pintype "output"))
    )
    (net (code "54") (name "PU7R") (class "Default")
      (node (ref "L4") (pin "7") (pinfunction "2A_7") (pintype "bidirectional"))
      (node (ref "U2") (pin "11") (pinfunction "PWM5_11") (pintype "output"))
    )
    (net (code "55") (name "PU8EN") (class "Default")
      (node (ref "L4") (pin "9") (pinfunction "3,4EN_9") (pintype "bidirectional"))
      (node (ref "U2") (pin "12") (pinfunction "PWM6_12") (pintype "output"))
    )
    (net (code "56") (name "PU8L") (class "Default")
      (node (ref "L4") (pin "10") (pinfunction "3A_10") (pintype "bidirectional"))
      (node (ref "U2") (pin "13") (pinfunction "PWM7_13") (pintype "output"))
    )
    (net (code "57") (name "PU8R") (class "Default")
      (node (ref "L4") (pin "15") (pinfunction "4A_15") (pintype "bidirectional"))
      (node (ref "U2") (pin "15") (pinfunction "PWM8_15") (pintype "output"))
    )
    (net (code "58") (name "PU9EN") (class "Default")
      (node (ref "L5") (pin "1") (pinfunction "1,2EN_1") (pintype "bidirectional"))
      (node (ref "U2") (pin "16") (pinfunction "PWM9_16") (pintype "output"))
    )
    (net (code "59") (name "PU9L") (class "Default")
      (node (ref "L5") (pin "2") (pinfunction "1A_2") (pintype "bidirectional"))
      (node (ref "U2") (pin "17") (pinfunction "PWM10_17") (pintype "output"))
    )
    (net (code "60") (name "PU9R") (class "Default")
      (node (ref "L5") (pin "7") (pinfunction "2A_7") (pintype "bidirectional"))
      (node (ref "U2") (pin "18") (pinfunction "PWM11_18") (pintype "output"))
    )
    (net (code "61") (name "PU10EN") (class "Default")
      (node (ref "L5") (pin "9") (pinfunction "3,4EN_9") (pintype "bidirectional"))
      (node (ref "U2") (pin "19") (pinfunction "PWM12_19") (pintype "output"))
    )
    (net (code "62") (name "PU10L") (class "Default")
      (node (ref "L5") (pin "10") (pinfunction "3A_10") (pintype "bidirectional"))
      (node (ref "U2") (pin "20") (pinfunction "PWM13_20") (pintype "output"))
    )
    (net (code "63") (name "PU10R") (class "Default")
      (node (ref "L5") (pin "15") (pinfunction "4A_15") (pintype "bidirectional"))
      (node (ref "U2") (pin "21") (pinfunction "PWM14_21") (pintype "output"))
    )
    (net (code "64") (name "RST") (class "Default")
      (node (ref "ESP1") (pin "1") (pinfunction "RST_1") (pintype "bidirectional"))
      (node (ref "J3") (pin "1") (pinfunction "1_1") (pintype "passive"))
    )
    (net (code "65") (name "RXD-ESP") (class "Default")
      (node (ref "ESP1") (pin "21") (pinfunction "RXD_21") (pintype "bidirectional"))
      (node (ref "J3") (pin "5") (pinfunction "5_5") (pintype "passive"))
    )
    (net (code "66") (name "SBUSY") (class "Default")
      (node (ref "SV2") (pin "2") (pinfunction "2_2") (pintype "passive"))
    )
    (net (code "67") (name "SCL") (class "Default")
      (node (ref "R2") (pin "2") (pinfunction "2_2") (pintype "passive"))
      (node (ref "TEENSY1") (pin "41") (pinfunction "19/A5/PWM/SCL0_41") (pintype "bidirectional"))
      (node (ref "U1") (pin "26") (pinfunction "SCL_26") (pintype "bidirectional"))
      (node (ref "U2") (pin "26") (pinfunction "SCL_26") (pintype "bidirectional"))
    )
    (net (code "68") (name "SCLK-ESP") (class "Default")
      (node (ref "ESP1") (pin "14") (pinfunction "SCLK_14") (pintype "bidirectional"))
      (node (ref "J3") (pin "11") (pinfunction "11_11") (pintype "passive"))
    )
    (net (code "69") (name "SDA") (class "Default")
      (node (ref "R1") (pin "2") (pinfunction "2_2") (pintype "passive"))
      (node (ref "TEENSY1") (pin "40") (pinfunction "18/A4/PWM/SDA0_40") (pintype "bidirectional"))
      (node (ref "U1") (pin "27") (pinfunction "SDA_27") (pintype "bidirectional"))
      (node (ref "U2") (pin "27") (pinfunction "SDA_27") (pintype "bidirectional"))
    )
    (net (code "70") (name "SIN") (class "Default")
      (node (ref "SV2") (pin "1") (pinfunction "1_1") (pintype "passive"))
    )
    (net (code "71") (name "SW1B") (class "Default")
      (node (ref "JP1") (pin "5") (pinfunction "5_5") (pintype "passive"))
    )
    (net (code "72") (name "SW1G") (class "Default")
      (node (ref "JP1") (pin "3") (pinfunction "3_3") (pintype "passive"))
    )
    (net (code "73") (name "SW1NC+") (class "Default")
      (node (ref "SV5") (pin "1") (pinfunction "1_1") (pintype "passive"))
    )
    (net (code "74") (name "SW1NC-") (class "Default")
      (node (ref "SV5") (pin "2") (pinfunction "2_2") (pintype "passive"))
    )
    (net (code "75") (name "SW1NO+") (class "Default")
      (node (ref "SV5") (pin "3") (pinfunction "3_3") (pintype "passive"))
    )
    (net (code "76") (name "SW1NO-") (class "Default")
      (node (ref "SV5") (pin "4") (pinfunction "4_4") (pintype "passive"))
    )
    (net (code "77") (name "SW1R") (class "Default")
      (node (ref "JP1") (pin "1") (pinfunction "1_1") (pintype "passive"))
    )
    (net (code "78") (name "SW2B") (class "Default")
      (node (ref "JP1") (pin "6") (pinfunction "6_6") (pintype "passive"))
    )
    (net (code "79") (name "SW2G") (class "Default")
      (node (ref "JP1") (pin "4") (pinfunction "4_4") (pintype "passive"))
    )
    (net (code "80") (name "SW2NC+") (class "Default")
      (node (ref "SV4") (pin "1") (pinfunction "1_1") (pintype "passive"))
    )
    (net (code "81") (name "SW2NC-") (class "Default")
      (node (ref "SV4") (pin "2") (pinfunction "2_2") (pintype "passive"))
    )
    (net (code "82") (name "SW2NO+") (class "Default")
      (node (ref "SV4") (pin "3") (pinfunction "3_3") (pintype "passive"))
    )
    (net (code "83") (name "SW2NO-") (class "Default")
      (node (ref "SV4") (pin "4") (pinfunction "4_4") (pintype "passive"))
    )
    (net (code "84") (name "SW2R") (class "Default")
      (node (ref "JP1") (pin "2") (pinfunction "2_2") (pintype "passive"))
    )
    (net (code "85") (name "TXD-ESP") (class "Default")
      (node (ref "ESP1") (pin "22") (pinfunction "TXD_22") (pintype "bidirectional"))
      (node (ref "J3") (pin "7") (pinfunction "7_7") (pintype "passive"))
    )
    (net (code "86") (name "unconnected-(C14-A-Pad1)") (class "Default")
      (node (ref "C14") (pin "1") (pinfunction "A_1") (pintype "passive"))
    )
    (net (code "87") (name "unconnected-(C14-B-Pad2)") (class "Default")
      (node (ref "C14") (pin "2") (pinfunction "B_2") (pintype "passive"))
    )
    (net (code "88") (name "unconnected-(C15-A-Pad1)") (class "Default")
      (node (ref "C15") (pin "1") (pinfunction "A_1") (pintype "passive"))
    )
    (net (code "89") (name "unconnected-(C15-B-Pad2)") (class "Default")
      (node (ref "C15") (pin "2") (pinfunction "B_2") (pintype "passive"))
    )
    (net (code "90") (name "unconnected-(C16-A-Pad1)") (class "Default")
      (node (ref "C16") (pin "1") (pinfunction "A_1") (pintype "passive"))
    )
    (net (code "91") (name "unconnected-(C16-B-Pad2)") (class "Default")
      (node (ref "C16") (pin "2") (pinfunction "B_2") (pintype "passive"))
    )
    (net (code "92") (name "unconnected-(SV3-Pad3)") (class "Default")
      (node (ref "SV3") (pin "3") (pinfunction "3_3") (pintype "passive"))
    )
    (net (code "93") (name "unconnected-(TEENSY1-0{slash}RX1{slash}MOSI1-Pad2)") (class "Default")
      (node (ref "TEENSY1") (pin "2") (pinfunction "0/RX1/MOSI1_2") (pintype "bidirectional"))
    )
    (net (code "94") (name "unconnected-(TEENSY1-1{slash}TX1{slash}MISO-Pad3)") (class "Default")
      (node (ref "TEENSY1") (pin "3") (pinfunction "1/TX1/MISO_3") (pintype "bidirectional"))
    )
    (net (code "95") (name "unconnected-(TEENSY1-2{slash}PWM-Pad4)") (class "Default")
      (node (ref "TEENSY1") (pin "4") (pinfunction "2/PWM_4") (pintype "bidirectional"))
    )
    (net (code "96") (name "unconnected-(TEENSY1-3{slash}PWM{slash}SCL2{slash}CAN0TX-Pad5)") (class "Default")
      (node (ref "TEENSY1") (pin "5") (pinfunction "3/PWM/SCL2/CAN0TX_5") (pintype "bidirectional"))
    )
    (net (code "97") (name "unconnected-(TEENSY1-4{slash}PWM{slash}SDA2{slash}CAN0RX-Pad6)") (class "Default")
      (node (ref "TEENSY1") (pin "6") (pinfunction "4/PWM/SDA2/CAN0RX_6") (pintype "bidirectional"))
    )
    (net (code "98") (name "unconnected-(TEENSY1-5{slash}PWM{slash}ALT-TX1{slash}ALT-MISO1-Pad7)") (class "Default")
      (node (ref "TEENSY1") (pin "7") (pinfunction "5/PWM/ALT-TX1/ALT-MISO1_7") (pintype "bidirectional"))
    )
    (net (code "99") (name "unconnected-(TEENSY1-6{slash}PWM-Pad8)") (class "Default")
      (node (ref "TEENSY1") (pin "8") (pinfunction "6/PWM_8") (pintype "bidirectional"))
    )
    (net (code "100") (name "unconnected-(TEENSY1-7{slash}PWM{slash}RX3{slash}ALT-SCL0{slash}ALT-MOSI0-Pad9)") (class "Default")
      (node (ref "TEENSY1") (pin "9") (pinfunction "7/PWM/RX3/ALT-SCL0/ALT-MOSI0_9") (pintype "bidirectional"))
    )
    (net (code "101") (name "unconnected-(TEENSY1-8{slash}PWM{slash}TX3{slash}ALT-SDA0{slash}ALT-MISO0-Pad10)") (class "Default")
      (node (ref "TEENSY1") (pin "10") (pinfunction "8/PWM/TX3/ALT-SDA0/ALT-MISO0_10") (pintype "bidirectional"))
    )
    (net (code "102") (name "unconnected-(TEENSY1-9{slash}PWM{slash}RX2{slash}CS0-1-Pad11)") (class "Default")
      (node (ref "TEENSY1") (pin "11") (pinfunction "9/PWM/RX2/CS0-1_11") (pintype "bidirectional"))
    )
    (net (code "103") (name "unconnected-(TEENSY1-10{slash}PWM{slash}TX2{slash}CS0-0-Pad12)") (class "Default")
      (node (ref "TEENSY1") (pin "12") (pinfunction "10/PWM/TX2/CS0-0_12") (pintype "bidirectional"))
    )
    (net (code "104") (name "unconnected-(TEENSY1-11{slash}MOSI0-Pad13)") (class "Default")
      (node (ref "TEENSY1") (pin "13") (pinfunction "11/MOSI0_13") (pintype "bidirectional"))
    )
    (net (code "105") (name "unconnected-(TEENSY1-12{slash}MISO0-Pad14)") (class "Default")
      (node (ref "TEENSY1") (pin "14") (pinfunction "12/MISO0_14") (pintype "bidirectional"))
    )
    (net (code "106") (name "unconnected-(TEENSY1-13{slash}LED{slash}ALT-PWM{slash}SCK0-Pad35)") (class "Default")
      (node (ref "TEENSY1") (pin "35") (pinfunction "13/LED/ALT-PWM/SCK0_35") (pintype "bidirectional"))
    )
    (net (code "107") (name "unconnected-(TEENSY1-14{slash}A0{slash}PWM{slash}ALT-SCK0-Pad36)") (class "Default")
      (node (ref "TEENSY1") (pin "36") (pinfunction "14/A0/PWM/ALT-SCK0_36") (pintype "bidirectional"))
    )
    (net (code "108") (name "unconnected-(TEENSY1-15{slash}A1{slash}CS0-4-Pad37)") (class "Default")
      (node (ref "TEENSY1") (pin "37") (pinfunction "15/A1/CS0-4_37") (pintype "bidirectional"))
    )
    (net (code "109") (name "unconnected-(TEENSY1-16{slash}A2{slash}PWM{slash}ALT-SCL0-Pad38)") (class "Default")
      (node (ref "TEENSY1") (pin "38") (pinfunction "16/A2/PWM/ALT-SCL0_38") (pintype "bidirectional"))
    )
    (net (code "110") (name "unconnected-(TEENSY1-17{slash}A3{slash}PWM{slash}ALT-SDA0-Pad39)") (class "Default")
      (node (ref "TEENSY1") (pin "39") (pinfunction "17/A3/PWM/ALT-SDA0_39") (pintype "bidirectional"))
    )
    (net (code "111") (name "unconnected-(TEENSY1-20{slash}A6{slash}PWM{slash}CS0-2{slash}ALT-SCK1-Pad42)") (class "Default")
      (node (ref "TEENSY1") (pin "42") (pinfunction "20/A6/PWM/CS0-2/ALT-SCK1_42") (pintype "bidirectional"))
    )
    (net (code "112") (name "unconnected-(TEENSY1-21{slash}A7{slash}PWM{slash}CS0-3{slash}ALT-MOSI1{slash}ALT-RX1-Pad43)") (class "Default")
      (node (ref "TEENSY1") (pin "43") (pinfunction "21/A7/PWM/CS0-3/ALT-MOSI1/ALT-RX1_43") (pintype "bidirectional"))
    )
    (net (code "113") (name "unconnected-(TEENSY1-22{slash}A8{slash}PWM-Pad44)") (class "Default")
      (node (ref "TEENSY1") (pin "44") (pinfunction "22/A8/PWM_44") (pintype "bidirectional"))
    )
    (net (code "114") (name "unconnected-(TEENSY1-23{slash}A9{slash}PWM-Pad45)") (class "Default")
      (node (ref "TEENSY1") (pin "45") (pinfunction "23/A9/PWM_45") (pintype "bidirectional"))
    )
    (net (code "115") (name "unconnected-(TEENSY1-24-Pad16)") (class "Default")
      (node (ref "TEENSY1") (pin "16") (pinfunction "24_16") (pintype "bidirectional"))
    )
    (net (code "116") (name "unconnected-(TEENSY1-25-Pad17)") (class "Default")
      (node (ref "TEENSY1") (pin "17") (pinfunction "25_17") (pintype "bidirectional"))
    )
    (net (code "117") (name "unconnected-(TEENSY1-26{slash}ALT-PWM{slash}ALT-TX1{slash}ALT-SCL2-Pad18)") (class "Default")
      (node (ref "TEENSY1") (pin "18") (pinfunction "26/ALT-PWM/ALT-TX1/ALT-SCL2_18") (pintype "bidirectional"))
    )
    (net (code "118") (name "unconnected-(TEENSY1-27{slash}ALT-RX1{slash}ALT-SCK0-Pad19)") (class "Default")
      (node (ref "TEENSY1") (pin "19") (pinfunction "27/ALT-RX1/ALT-SCK0_19") (pintype "bidirectional"))
    )
    (net (code "119") (name "unconnected-(TEENSY1-28{slash}ALT-MOSI0-Pad20)") (class "Default")
      (node (ref "TEENSY1") (pin "20") (pinfunction "28/ALT-MOSI0_20") (pintype "bidirectional"))
    )
    (net (code "120") (name "unconnected-(TEENSY1-29{slash}PWM{slash}ALT-CAN0TX-Pad21)") (class "Default")
      (node (ref "TEENSY1") (pin "21") (pinfunction "29/PWM/ALT-CAN0TX_21") (pintype "bidirectional"))
    )
    (net (code "121") (name "unconnected-(TEENSY1-30{slash}PWM{slash}ALT-CAN0RX-Pad22)") (class "Default")
      (node (ref "TEENSY1") (pin "22") (pinfunction "30/PWM/ALT-CAN0RX_22") (pintype "bidirectional"))
    )
    (net (code "122") (name "unconnected-(TEENSY1-31{slash}A12{slash}PWM{slash}RX4{slash}CS1-0-Pad23)") (class "Default")
      (node (ref "TEENSY1") (pin "23") (pinfunction "31/A12/PWM/RX4/CS1-0_23") (pintype "bidirectional"))
    )
    (net (code "123") (name "unconnected-(TEENSY1-32{slash}A13{slash}PWM{slash}TX4{slash}SCK1-Pad24)") (class "Default")
      (node (ref "TEENSY1") (pin "24") (pinfunction "32/A13/PWM/TX4/SCK1_24") (pintype "bidirectional"))
    )
    (net (code "124") (name "unconnected-(TEENSY1-33{slash}A14{slash}CAN1TX{slash}TX5{slash}ALT-SCL0-Pad25)") (class "Default")
      (node (ref "TEENSY1") (pin "25") (pinfunction "33/A14/CAN1TX/TX5/ALT-SCL0_25") (pintype "bidirectional"))
    )
    (net (code "125") (name "unconnected-(TEENSY1-34{slash}A15{slash}CAN1RX{slash}RX5{slash}ALT-SDA0-Pad26)") (class "Default")
      (node (ref "TEENSY1") (pin "26") (pinfunction "34/A15/CAN1RX/RX5/ALT-SDA0_26") (pintype "bidirectional"))
    )
    (net (code "126") (name "unconnected-(TEENSY1-35{slash}A16{slash}PWM-Pad27)") (class "Default")
      (node (ref "TEENSY1") (pin "27") (pinfunction "35/A16/PWM_27") (pintype "bidirectional"))
    )
    (net (code "127") (name "unconnected-(TEENSY1-36{slash}A17{slash}PWM-Pad28)") (class "Default")
      (node (ref "TEENSY1") (pin "28") (pinfunction "36/A17/PWM_28") (pintype "bidirectional"))
    )
    (net (code "128") (name "unconnected-(TEENSY1-37{slash}A18{slash}PWM{slash}SCL1-Pad29)") (class "Default")
      (node (ref "TEENSY1") (pin "29") (pinfunction "37/A18/PWM/SCL1_29") (pintype "bidirectional"))
    )
    (net (code "129") (name "unconnected-(TEENSY1-38{slash}A19{slash}PWM{slash}SDA1-Pad30)") (class "Default")
      (node (ref "TEENSY1") (pin "30") (pinfunction "38/A19/PWM/SDA1_30") (pintype "bidirectional"))
    )
    (net (code "130") (name "unconnected-(TEENSY1-39{slash}A20{slash}ALT-MISO0-Pad31)") (class "Default")
      (node (ref "TEENSY1") (pin "31") (pinfunction "39/A20/ALT-MISO0_31") (pintype "bidirectional"))
    )
    (net (code "131") (name "unconnected-(TEENSY1-DAC0-Pad32)") (class "Default")
      (node (ref "TEENSY1") (pin "32") (pinfunction "DAC0_32") (pintype "bidirectional"))
    )
    (net (code "132") (name "unconnected-(TEENSY1-DAC1-Pad33)") (class "Default")
      (node (ref "TEENSY1") (pin "33") (pinfunction "DAC1_33") (pintype "bidirectional"))
    )
    (net (code "133") (name "unconnected-(U1-#OE-Pad23)") (class "Default")
      (node (ref "U1") (pin "23") (pinfunction "#OE_23") (pintype "input"))
    )
    (net (code "134") (name "unconnected-(U1-A0-Pad1)") (class "Default")
      (node (ref "U1") (pin "1") (pinfunction "A0_1") (pintype "bidirectional"))
    )
    (net (code "135") (name "unconnected-(U1-A1-Pad2)") (class "Default")
      (node (ref "U1") (pin "2") (pinfunction "A1_2") (pintype "bidirectional"))
    )
    (net (code "136") (name "unconnected-(U1-A2-Pad3)") (class "Default")
      (node (ref "U1") (pin "3") (pinfunction "A2_3") (pintype "bidirectional"))
    )
    (net (code "137") (name "unconnected-(U1-A3-Pad4)") (class "Default")
      (node (ref "U1") (pin "4") (pinfunction "A3_4") (pintype "bidirectional"))
    )
    (net (code "138") (name "unconnected-(U1-A4-Pad5)") (class "Default")
      (node (ref "U1") (pin "5") (pinfunction "A4_5") (pintype "bidirectional"))
    )
    (net (code "139") (name "unconnected-(U1-A5-Pad24)") (class "Default")
      (node (ref "U1") (pin "24") (pinfunction "A5_24") (pintype "bidirectional"))
    )
    (net (code "140") (name "unconnected-(U1-EXTCLK-Pad25)") (class "Default")
      (node (ref "U1") (pin "25") (pinfunction "EXTCLK_25") (pintype "input"))
    )
    (net (code "141") (name "unconnected-(U1-PWM15-Pad22)") (class "Default")
      (node (ref "U1") (pin "22") (pinfunction "PWM15_22") (pintype "output"))
    )
    (net (code "142") (name "unconnected-(U2-#OE-Pad23)") (class "Default")
      (node (ref "U2") (pin "23") (pinfunction "#OE_23") (pintype "input"))
    )
    (net (code "143") (name "unconnected-(U2-A1-Pad2)") (class "Default")
      (node (ref "U2") (pin "2") (pinfunction "A1_2") (pintype "bidirectional"))
    )
    (net (code "144") (name "unconnected-(U2-A2-Pad3)") (class "Default")
      (node (ref "U2") (pin "3") (pinfunction "A2_3") (pintype "bidirectional"))
    )
    (net (code "145") (name "unconnected-(U2-A3-Pad4)") (class "Default")
      (node (ref "U2") (pin "4") (pinfunction "A3_4") (pintype "bidirectional"))
    )
    (net (code "146") (name "unconnected-(U2-A4-Pad5)") (class "Default")
      (node (ref "U2") (pin "5") (pinfunction "A4_5") (pintype "bidirectional"))
    )
    (net (code "147") (name "unconnected-(U2-A5-Pad24)") (class "Default")
      (node (ref "U2") (pin "24") (pinfunction "A5_24") (pintype "bidirectional"))
    )
    (net (code "148") (name "unconnected-(U2-EXTCLK-Pad25)") (class "Default")
      (node (ref "U2") (pin "25") (pinfunction "EXTCLK_25") (pintype "input"))
    )
    (net (code "149") (name "unconnected-(U2-PWM15-Pad22)") (class "Default")
      (node (ref "U2") (pin "22") (pinfunction "PWM15_22") (pintype "output"))
    )
    (net (code "150") (name "unconnected-(U3A-+IN-Pad3)") (class "Default")
      (node (ref "U3") (pin "3") (pinfunction "+IN_3") (pintype "input"))
    )
    (net (code "151") (name "unconnected-(U3A--IN-Pad2)") (class "Default")
      (node (ref "U3") (pin "2") (pinfunction "-IN_2") (pintype "input"))
    )
    (net (code "152") (name "unconnected-(U3A-OUT-Pad1)") (class "Default")
      (node (ref "U3") (pin "1") (pinfunction "OUT_1") (pintype "output"))
    )
    (net (code "153") (name "unconnected-(U3B-+IN-Pad10)") (class "Default")
      (node (ref "U3") (pin "10") (pinfunction "+IN_10") (pintype "input"))
    )
    (net (code "154") (name "unconnected-(U3B--IN-Pad9)") (class "Default")
      (node (ref "U3") (pin "9") (pinfunction "-IN_9") (pintype "input"))
    )
    (net (code "155") (name "unconnected-(U3B-OUT-Pad8)") (class "Default")
      (node (ref "U3") (pin "8") (pinfunction "OUT_8") (pintype "output"))
    )
    (net (code "156") (name "unconnected-(U3C-+IN-Pad5)") (class "Default")
      (node (ref "U3") (pin "5") (pinfunction "+IN_5") (pintype "input"))
    )
    (net (code "157") (name "unconnected-(U3C--IN-Pad6)") (class "Default")
      (node (ref "U3") (pin "6") (pinfunction "-IN_6") (pintype "input"))
    )
    (net (code "158") (name "unconnected-(U3C-OUT-Pad7)") (class "Default")
      (node (ref "U3") (pin "7") (pinfunction "OUT_7") (pintype "output"))
    )
    (net (code "159") (name "unconnected-(U3D-+IN-Pad12)") (class "Default")
      (node (ref "U3") (pin "12") (pinfunction "+IN_12") (pintype "input"))
    )
    (net (code "160") (name "unconnected-(U3D--IN-Pad13)") (class "Default")
      (node (ref "U3") (pin "13") (pinfunction "-IN_13") (pintype "input"))
    )
    (net (code "161") (name "unconnected-(U3D-OUT-Pad14)") (class "Default")
      (node (ref "U3") (pin "14") (pinfunction "OUT_14") (pintype "output"))
    )
    (net (code "162") (name "unconnected-(U3E-P$V+-Pad4)") (class "Default")
      (node (ref "U3") (pin "4") (pinfunction "P$V+_4") (pintype "bidirectional"))
    )
    (net (code "163") (name "unconnected-(U3E-P$V--Pad11)") (class "Default")
      (node (ref "U3") (pin "11") (pinfunction "P$V-_11") (pintype "bidirectional"))
    )
    (net (code "164") (name "{slash}RESET") (class "Default")
      (node (ref "SV2") (pin "3") (pinfunction "3_3") (pintype "passive"))
    )
  )
)
